# Sender.net
KiCad netlist of a schematic drawn in EAGLE
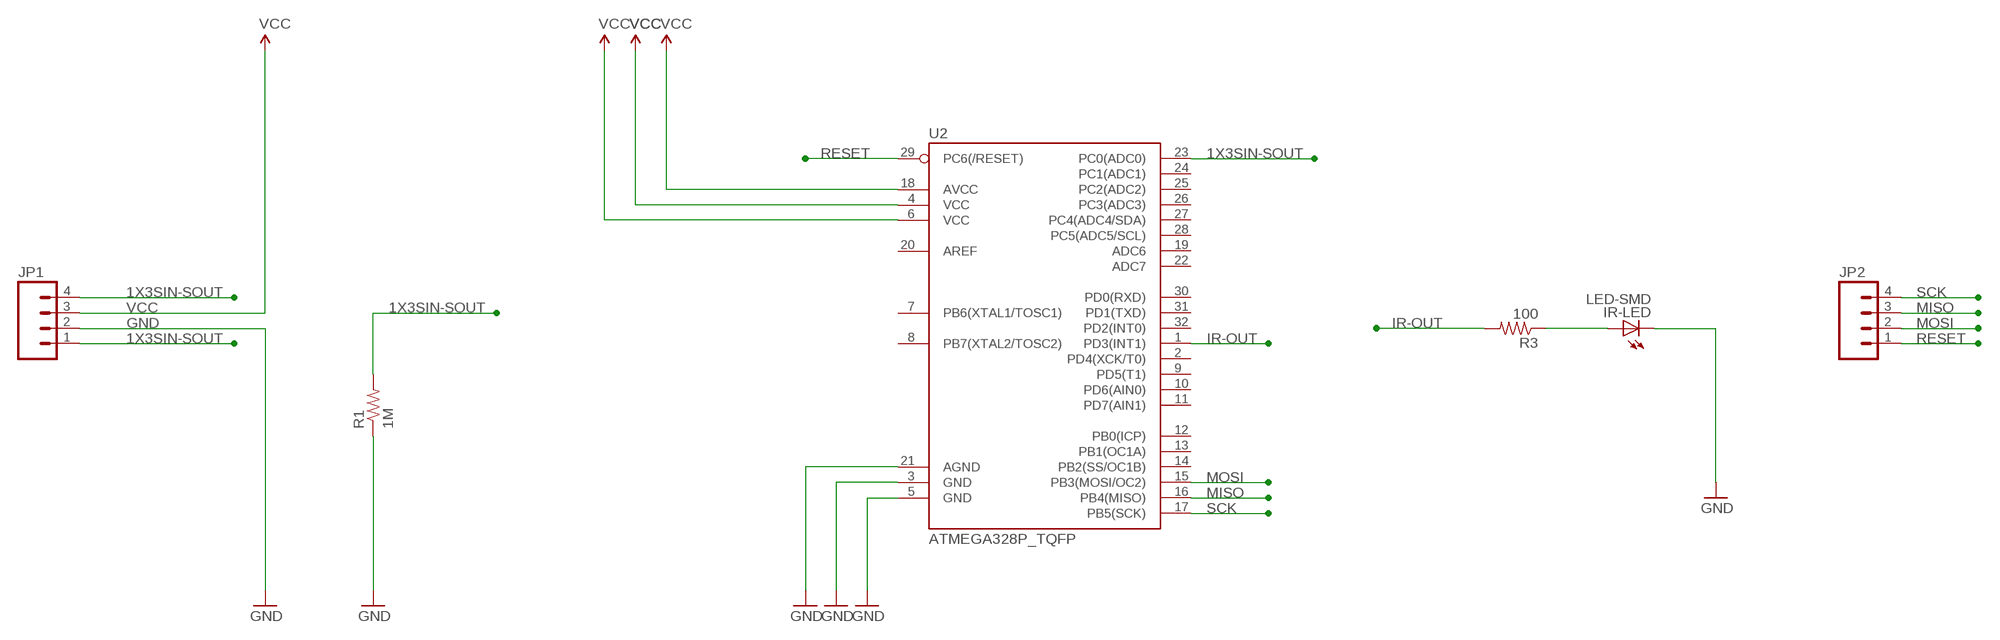
[diagram p0: schematic, sheet 1]

(export (version "E")
  (design (tool "Eeschema 10.0.6"))
  (components
    (comp (ref "IR-LED")
      (value "LED-SMD")
      (footprint "eagle-import:LED5MM-SMD")
      (libsource (lib "eagle-import") (part "LED-SMD"))
    )
    (comp (ref "JP1")
      (value "M04PTH")
      (footprint "eagle-import:1X04")
      (libsource (lib "eagle-import") (part "M04PTH"))
    )
    (comp (ref "JP2")
      (value "M04PTH")
      (footprint "eagle-import:1X04")
      (libsource (lib "eagle-import") (part "M04PTH"))
    )
    (comp (ref "R1")
      (value "1M")
      (footprint "eagle-import:R0603")
      (libsource (lib "eagle-import") (part "R-US_R0603"))
    )
    (comp (ref "R3")
      (value "100")
      (footprint "eagle-import:R0603")
      (libsource (lib "eagle-import") (part "R-US_R0603"))
    )
    (comp (ref "U2")
      (value "ATMEGA328P_TQFP")
      (footprint "eagle-import:TQFP32-08")
      (libsource (lib "eagle-import") (part "ATMEGA328P_TQFP"))
    )
  )
  (nets
    (net (code "1") (name "/1X3SIN-SOUT") (class "Default")
      (node (ref "JP1") (pin "1") (pinfunction "1_1") (pintype "passive"))
      (node (ref "JP1") (pin "4") (pinfunction "4_4") (pintype "passive"))
      (node (ref "R1") (pin "2") (pinfunction "2_2") (pintype "passive"))
      (node (ref "U2") (pin "23") (pinfunction "PC0(ADC0)_23") (pintype "bidirectional"))
    )
    (net (code "2") (name "/IR-OUT") (class "Default")
      (node (ref "R3") (pin "2") (pinfunction "2_2") (pintype "passive"))
      (node (ref "U2") (pin "1") (pinfunction "PD3(INT1)_1") (pintype "bidirectional"))
    )
    (net (code "3") (name "/MISO") (class "Default")
      (node (ref "JP2") (pin "3") (pinfunction "3_3") (pintype "passive"))
      (node (ref "U2") (pin "16") (pinfunction "PB4(MISO)_16") (pintype "bidirectional"))
    )
    (net (code "4") (name "/MOSI") (class "Default")
      (node (ref "JP2") (pin "2") (pinfunction "2_2") (pintype "passive"))
      (node (ref "U2") (pin "15") (pinfunction "PB3(MOSI/OC2)_15") (pintype "bidirectional"))
    )
    (net (code "5") (name "/RESET") (class "Default")
      (node (ref "JP2") (pin "1") (pinfunction "1_1") (pintype "passive"))
      (node (ref "U2") (pin "29") (pinfunction "PC6(/RESET)_29") (pintype "bidirectional"))
    )
    (net (code "6") (name "/SCK") (class "Default")
      (node (ref "JP2") (pin "4") (pinfunction "4_4") (pintype "passive"))
      (node (ref "U2") (pin "17") (pinfunction "PB5(SCK)_17") (pintype "bidirectional"))
    )
    (net (code "7") (name "GND") (class "Default")
      (node (ref "IR-LED") (pin "CATHODE") (pinfunction "C_CATHODE") (pintype "passive"))
      (node (ref "JP1") (pin "2") (pinfunction "2_2") (pintype "passive"))
      (node (ref "R1") (pin "1") (pinfunction "1_1") (pintype "passive"))
      (node (ref "U2") (pin "21") (pinfunction "AGND_21") (pintype "bidirectional"))
      (node (ref "U2") (pin "3") (pinfunction "GND_3") (pintype "bidirectional"))
      (node (ref "U2") (pin "5") (pinfunction "GND_5") (pintype "bidirectional"))
    )
    (net (code "8") (name "Net-(IR-LED-A)") (class "Default")
      (node (ref "IR-LED") (pin "ANODE") (pinfunction "A_ANODE") (pintype "passive"))
      (node (ref "R3") (pin "1") (pinfunction "1_1") (pintype "passive"))
    )
    (net (code "9") (name "VCC") (class "Default")
      (node (ref "JP1") (pin "3") (pinfunction "3_3") (pintype "passive"))
      (node (ref "U2") (pin "18") (pinfunction "AVCC_18") (pintype "bidirectional"))
      (node (ref "U2") (pin "4") (pinfunction "VCC_4") (pintype "bidirectional"))
      (node (ref "U2") (pin "6") (pinfunction "VCC_6") (pintype "bidirectional"))
    )
    (net (code "10") (name "unconnected-(U2-ADC6-Pad19)") (class "Default")
      (node (ref "U2") (pin "19") (pinfunction "ADC6_19") (pintype "bidirectional"))
    )
    (net (code "11") (name "unconnected-(U2-ADC7-Pad22)") (class "Default")
      (node (ref "U2") (pin "22") (pinfunction "ADC7_22") (pintype "bidirectional"))
    )
    (net (code "12") (name "unconnected-(U2-AREF-Pad20)") (class "Default")
      (node (ref "U2") (pin "20") (pinfunction "AREF_20") (pintype "bidirectional"))
    )
    (net (code "13") (name "unconnected-(U2-PB0(ICP)-Pad12)") (class "Default")
      (node (ref "U2") (pin "12") (pinfunction "PB0(ICP)_12") (pintype "bidirectional"))
    )
    (net (code "14") (name "unconnected-(U2-PB1(OC1A)-Pad13)") (class "Default")
      (node (ref "U2") (pin "13") (pinfunction "PB1(OC1A)_13") (pintype "bidirectional"))
    )
    (net (code "15") (name "unconnected-(U2-PB2(SS{slash}OC1B)-Pad14)") (class "Default")
      (node (ref "U2") (pin "14") (pinfunction "PB2(SS/OC1B)_14") (pintype "bidirectional"))
    )
    (net (code "16") (name "unconnected-(U2-PB6(XTAL1{slash}TOSC1)-Pad7)") (class "Default")
      (node (ref "U2") (pin "7") (pinfunction "PB6(XTAL1/TOSC1)_7") (pintype "bidirectional"))
    )
    (net (code "17") (name "unconnected-(U2-PB7(XTAL2{slash}TOSC2)-Pad8)") (class "Default")
      (node (ref "U2") (pin "8") (pinfunction "PB7(XTAL2/TOSC2)_8") (pintype "bidirectional"))
    )
    (net (code "18") (name "unconnected-(U2-PC1(ADC1)-Pad24)") (class "Default")
      (node (ref "U2") (pin "24") (pinfunction "PC1(ADC1)_24") (pintype "bidirectional"))
    )
    (net (code "19") (name "unconnected-(U2-PC2(ADC2)-Pad25)") (class "Default")
      (node (ref "U2") (pin "25") (pinfunction "PC2(ADC2)_25") (pintype "bidirectional"))
    )
    (net (code "20") (name "unconnected-(U2-PC3(ADC3)-Pad26)") (class "Default")
      (node (ref "U2") (pin "26") (pinfunction "PC3(ADC3)_26") (pintype "bidirectional"))
    )
    (net (code "21") (name "unconnected-(U2-PC4(ADC4{slash}SDA)-Pad27)") (class "Default")
      (node (ref "U2") (pin "27") (pinfunction "PC4(ADC4/SDA)_27") (pintype "bidirectional"))
    )
    (net (code "22") (name "unconnected-(U2-PC5(ADC5{slash}SCL)-Pad28)") (class "Default")
      (node (ref "U2") (pin "28") (pinfunction "PC5(ADC5/SCL)_28") (pintype "bidirectional"))
    )
    (net (code "23") (name "unconnected-(U2-PD0(RXD)-Pad30)") (class "Default")
      (node (ref "U2") (pin "30") (pinfunction "PD0(RXD)_30") (pintype "bidirectional"))
    )
    (net (code "24") (name "unconnected-(U2-PD1(TXD)-Pad31)") (class "Default")
      (node (ref "U2") (pin "31") (pinfunction "PD1(TXD)_31") (pintype "bidirectional"))
    )
    (net (code "25") (name "unconnected-(U2-PD2(INT0)-Pad32)") (class "Default")
      (node (ref "U2") (pin "32") (pinfunction "PD2(INT0)_32") (pintype "bidirectional"))
    )
    (net (code "26") (name "unconnected-(U2-PD4(XCK{slash}T0)-Pad2)") (class "Default")
      (node (ref "U2") (pin "2") (pinfunction "PD4(XCK/T0)_2") (pintype "bidirectional"))
    )
    (net (code "27") (name "unconnected-(U2-PD5(T1)-Pad9)") (class "Default")
      (node (ref "U2") (pin "9") (pinfunction "PD5(T1)_9") (pintype "bidirectional"))
    )
    (net (code "28") (name "unconnected-(U2-PD6(AIN0)-Pad10)") (class "Default")
      (node (ref "U2") (pin "10") (pinfunction "PD6(AIN0)_10") (pintype "bidirectional"))
    )
    (net (code "29") (name "unconnected-(U2-PD7(AIN1)-Pad11)") (class "Default")
      (node (ref "U2") (pin "11") (pinfunction "PD7(AIN1)_11") (pintype "bidirectional"))
    )
  )
)
